# Power.net
KiCad netlist of a schematic drawn in Altium Designer
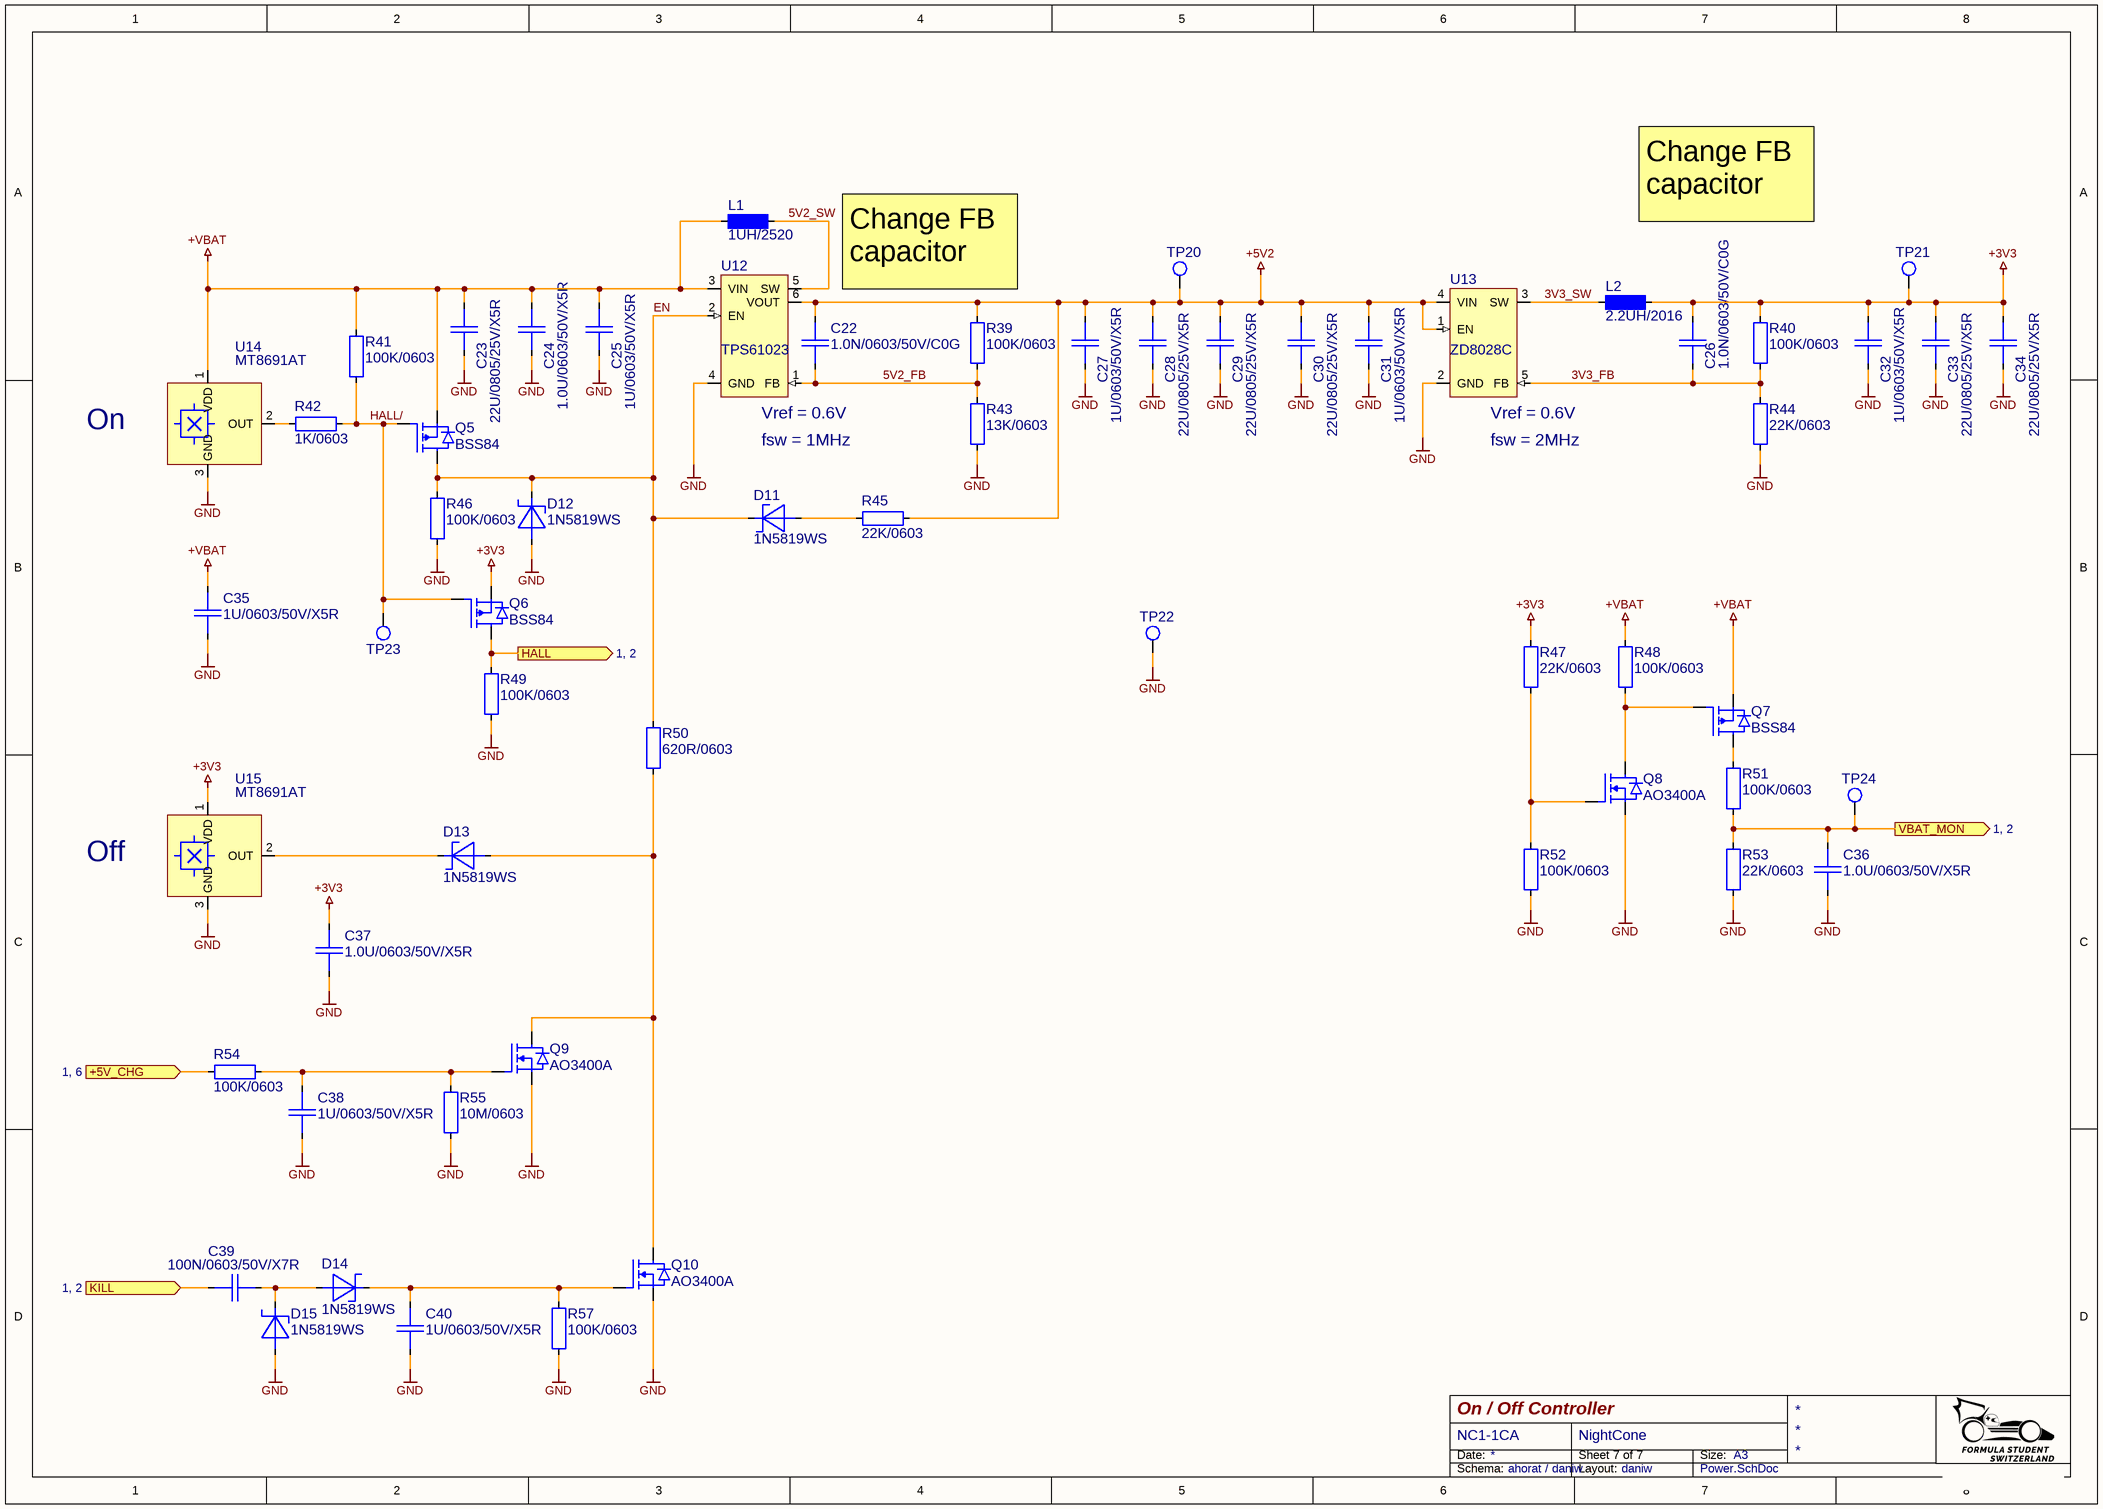
[diagram p0: Power.SchDoc]

(export (version "E")
  (design (tool "Eeschema 10.0.6"))
  (components
    (comp (ref "C22")
      (value "1.0N/0603/50V/C0G")
      (footprint "CAP0603_C0G")
      (description "CAP SM 0603 1.0nF 50V C0G")
      (fields (field (name "MANUFACTURER") "GENERIC"))
      (libsource (lib "daniw_altium_lib") (part "C"))
    )
    (comp (ref "C23")
      (value "22U/0805/25V/X5R")
      (footprint "CAP0805_X7R")
      (description "CAP SM 0805 22uF 25V X5R")
      (fields (field (name "MANUFACTURER") "GENERIC"))
      (libsource (lib "daniw_altium_lib") (part "C"))
    )
    (comp (ref "C24")
      (value "1.0U/0603/50V/X5R")
      (footprint "CAP0603_X7R")
      (description "CAP SM 0603 1.0uF 50V X5R")
      (fields (field (name "MANUFACTURER") "GENERIC"))
      (libsource (lib "daniw_altium_lib") (part "C"))
    )
    (comp (ref "C25")
      (value "1U/0603/50V/X5R")
      (footprint "CAP0603_X7R")
      (description "CAP SM 0603 1.0uF 50V X5R")
      (fields (field (name "MANUFACTURER") "GENERIC"))
      (libsource (lib "daniw_altium_lib") (part "C"))
    )
    (comp (ref "C26")
      (value "1.0N/0603/50V/C0G")
      (footprint "CAP0603_C0G")
      (description "CAP SM 0603 1.0nF 50V C0G")
      (fields (field (name "MANUFACTURER") "GENERIC"))
      (libsource (lib "daniw_altium_lib") (part "C"))
    )
    (comp (ref "C27")
      (value "1U/0603/50V/X5R")
      (footprint "CAP0603_X7R")
      (description "CAP SM 0603 1.0uF 50V X5R")
      (fields (field (name "MANUFACTURER") "GENERIC"))
      (libsource (lib "daniw_altium_lib") (part "C"))
    )
    (comp (ref "C28")
      (value "22U/0805/25V/X5R")
      (footprint "CAP0805_X7R")
      (description "CAP SM 0805 22uF 25V X5R")
      (fields (field (name "MANUFACTURER") "GENERIC"))
      (libsource (lib "daniw_altium_lib") (part "C"))
    )
    (comp (ref "C29")
      (value "22U/0805/25V/X5R")
      (footprint "CAP0805_X7R")
      (description "CAP SM 0805 22uF 25V X5R")
      (fields (field (name "MANUFACTURER") "GENERIC"))
      (libsource (lib "daniw_altium_lib") (part "C"))
    )
    (comp (ref "C30")
      (value "22U/0805/25V/X5R")
      (footprint "CAP0805_X7R")
      (description "CAP SM 0805 22uF 25V X5R")
      (fields (field (name "MANUFACTURER") "GENERIC"))
      (libsource (lib "daniw_altium_lib") (part "C"))
    )
    (comp (ref "C31")
      (value "1U/0603/50V/X5R")
      (footprint "CAP0603_X7R")
      (description "CAP SM 0603 1.0uF 50V X5R")
      (fields (field (name "MANUFACTURER") "GENERIC"))
      (libsource (lib "daniw_altium_lib") (part "C"))
    )
    (comp (ref "C32")
      (value "1U/0603/50V/X5R")
      (footprint "CAP0603_X7R")
      (description "CAP SM 0603 1.0uF 50V X5R")
      (fields (field (name "MANUFACTURER") "GENERIC"))
      (libsource (lib "daniw_altium_lib") (part "C"))
    )
    (comp (ref "C33")
      (value "22U/0805/25V/X5R")
      (footprint "CAP0805_X7R")
      (description "CAP SM 0805 22uF 25V X5R")
      (fields (field (name "MANUFACTURER") "GENERIC"))
      (libsource (lib "daniw_altium_lib") (part "C"))
    )
    (comp (ref "C34")
      (value "22U/0805/25V/X5R")
      (footprint "CAP0805_X7R")
      (description "CAP SM 0805 22uF 25V X5R")
      (fields (field (name "MANUFACTURER") "GENERIC"))
      (libsource (lib "daniw_altium_lib") (part "C"))
    )
    (comp (ref "C35")
      (value "1U/0603/50V/X5R")
      (footprint "CAP0603_X7R")
      (description "CAP SM 0603 1.0uF 50V X5R")
      (fields (field (name "MANUFACTURER") "GENERIC"))
      (libsource (lib "daniw_altium_lib") (part "C"))
    )
    (comp (ref "C36")
      (value "1.0U/0603/50V/X5R")
      (footprint "CAP0603_X7R")
      (description "CAP SM 0603 1.0uF 50V X5R")
      (fields (field (name "MANUFACTURER") "GENERIC"))
      (libsource (lib "daniw_altium_lib") (part "C"))
    )
    (comp (ref "C37")
      (value "1.0U/0603/50V/X5R")
      (footprint "CAP0603_X7R")
      (description "CAP SM 0603 1.0uF 50V X5R")
      (fields (field (name "MANUFACTURER") "GENERIC"))
      (libsource (lib "daniw_altium_lib") (part "C"))
    )
    (comp (ref "C38")
      (value "1U/0603/50V/X5R")
      (footprint "CAP0603_X7R")
      (description "CAP SM 0603 1.0uF 50V X5R")
      (fields (field (name "MANUFACTURER") "GENERIC"))
      (libsource (lib "daniw_altium_lib") (part "C"))
    )
    (comp (ref "C39")
      (value "100N/0603/50V/X7R")
      (footprint "CAP0603_X7R")
      (description "CAP SM 0603 100nF 50V X7R")
      (fields (field (name "MANUFACTURER") "GENERIC"))
      (libsource (lib "daniw_altium_lib") (part "C"))
    )
    (comp (ref "C40")
      (value "1U/0603/50V/X5R")
      (footprint "CAP0603_X7R")
      (description "CAP SM 0603 1.0uF 50V X5R")
      (fields (field (name "MANUFACTURER") "GENERIC"))
      (libsource (lib "daniw_altium_lib") (part "C"))
    )
    (comp (ref "D11")
      (value "1N5819WS")
      (footprint "SOD2513X100")
      (description "40V 600mV@1A 1A SOD-323 Schottky Barrier Diodes (SBD) ROHS")
      (fields (field (name "MANUFACTURER") "GENERIC"))
      (libsource (lib "daniw_altium_lib") (part "D_Schottky"))
    )
    (comp (ref "D12")
      (value "1N5819WS")
      (footprint "SOD2513X100")
      (description "40V 600mV@1A 1A SOD-323 Schottky Barrier Diodes (SBD) ROHS")
      (fields (field (name "MANUFACTURER") "GENERIC"))
      (libsource (lib "daniw_altium_lib") (part "D_Schottky"))
    )
    (comp (ref "D13")
      (value "1N5819WS")
      (footprint "SOD2513X100")
      (description "40V 600mV@1A 1A SOD-323 Schottky Barrier Diodes (SBD) ROHS")
      (fields (field (name "MANUFACTURER") "GENERIC"))
      (libsource (lib "daniw_altium_lib") (part "D_Schottky"))
    )
    (comp (ref "D14")
      (value "1N5819WS")
      (footprint "SOD2513X100")
      (description "40V 600mV@1A 1A SOD-323 Schottky Barrier Diodes (SBD) ROHS")
      (fields (field (name "MANUFACTURER") "GENERIC"))
      (libsource (lib "daniw_altium_lib") (part "D_Schottky"))
    )
    (comp (ref "D15")
      (value "1N5819WS")
      (footprint "SOD2513X100")
      (description "40V 600mV@1A 1A SOD-323 Schottky Barrier Diodes (SBD) ROHS")
      (fields (field (name "MANUFACTURER") "GENERIC"))
      (libsource (lib "daniw_altium_lib") (part "D_Schottky"))
    )
    (comp (ref "L1")
      (value "1UH/2520")
      (footprint "INDM2520X10")
      (description "1UH 2520 Shielded Inductor SMD")
      (fields (field (name "MANUFACTURER") "GENERIC"))
      (libsource (lib "daniw_altium_lib") (part "L"))
    )
    (comp (ref "L2")
      (value "2.2UH/2016")
      (footprint "INDM2016X10")
      (description "2.2UH 2016 Shielded Inductor SMD")
      (fields (field (name "MANUFACTURER") "GENERIC"))
      (libsource (lib "daniw_altium_lib") (part "L"))
    )
    (comp (ref "Q5")
      (value "BSS84")
      (footprint "SOT2395P280X125-3-SE")
      (description "50V P-Channel MOSFET")
      (fields (field (name "MANUFACTURER") "GENERIC"))
      (libsource (lib "daniw_altium_lib") (part "MOSFET P_SOT23"))
    )
    (comp (ref "Q6")
      (value "BSS84")
      (footprint "SOT2395P280X125-3-SE")
      (description "50V P-Channel MOSFET")
      (fields (field (name "MANUFACTURER") "GENERIC"))
      (libsource (lib "daniw_altium_lib") (part "MOSFET P_SOT23"))
    )
    (comp (ref "Q7")
      (value "BSS84")
      (footprint "SOT2395P280X125-3-SE")
      (description "50V P-Channel MOSFET")
      (fields (field (name "MANUFACTURER") "GENERIC"))
      (libsource (lib "daniw_altium_lib") (part "MOSFET P_SOT23"))
    )
    (comp (ref "Q8")
      (value "AO3400A")
      (footprint "SOT2395P280X125-3-SE")
      (description "30V N-Channel MOSFET")
      (fields (field (name "MANUFACTURER") "Alpha & Omega Semiconductor"))
      (libsource (lib "daniw_altium_lib") (part "MOSFET N_SOT23"))
    )
    (comp (ref "Q9")
      (value "AO3400A")
      (footprint "SOT2395P280X125-3-SE")
      (description "30V N-Channel MOSFET")
      (fields (field (name "MANUFACTURER") "Alpha & Omega Semiconductor"))
      (libsource (lib "daniw_altium_lib") (part "MOSFET N_SOT23"))
    )
    (comp (ref "Q10")
      (value "AO3400A")
      (footprint "SOT2395P280X125-3-SE")
      (description "30V N-Channel MOSFET")
      (fields (field (name "MANUFACTURER") "Alpha & Omega Semiconductor"))
      (libsource (lib "daniw_altium_lib") (part "MOSFET N_SOT23"))
    )
    (comp (ref "R39")
      (value "100K/0603")
      (footprint "R0603-0.40-WW")
      (description "RES SM 0603 100K")
      (fields (field (name "MANUFACTURER") "GENERIC"))
      (libsource (lib "daniw_altium_lib") (part "R"))
    )
    (comp (ref "R40")
      (value "100K/0603")
      (footprint "R0603-0.40-WW")
      (description "RES SM 0603 100K")
      (fields (field (name "MANUFACTURER") "GENERIC"))
      (libsource (lib "daniw_altium_lib") (part "R"))
    )
    (comp (ref "R41")
      (value "100K/0603")
      (footprint "R0603-0.40-WW")
      (description "RES SM 0603 100K")
      (fields (field (name "MANUFACTURER") "GENERIC"))
      (libsource (lib "daniw_altium_lib") (part "R"))
    )
    (comp (ref "R42")
      (value "1K/0603")
      (footprint "R0603-0.40-WW")
      (description "RES SM 0603 1K")
      (fields (field (name "MANUFACTURER") "GENERIC"))
      (libsource (lib "daniw_altium_lib") (part "R"))
    )
    (comp (ref "R43")
      (value "13K/0603")
      (footprint "R0603-0.40-WW")
      (description "RES SM 0603 13K")
      (fields (field (name "MANUFACTURER") "GENERIC"))
      (libsource (lib "daniw_altium_lib") (part "R"))
    )
    (comp (ref "R44")
      (value "22K/0603")
      (footprint "R0603-0.40-WW")
      (description "RES SM 0603 22K")
      (fields (field (name "MANUFACTURER") "GENERIC"))
      (libsource (lib "daniw_altium_lib") (part "R"))
    )
    (comp (ref "R45")
      (value "22K/0603")
      (footprint "R0603-0.40-WW")
      (description "RES SM 0603 22K")
      (fields (field (name "MANUFACTURER") "GENERIC"))
      (libsource (lib "daniw_altium_lib") (part "R"))
    )
    (comp (ref "R46")
      (value "100K/0603")
      (footprint "R0603-0.40-WW")
      (description "RES SM 0603 100K")
      (fields (field (name "MANUFACTURER") "GENERIC"))
      (libsource (lib "daniw_altium_lib") (part "R"))
    )
    (comp (ref "R47")
      (value "22K/0603")
      (footprint "R0603-0.40-WW")
      (description "RES SM 0603 22K")
      (fields (field (name "MANUFACTURER") "GENERIC"))
      (libsource (lib "daniw_altium_lib") (part "R"))
    )
    (comp (ref "R48")
      (value "100K/0603")
      (footprint "R0603-0.40-WW")
      (description "RES SM 0603 100K")
      (fields (field (name "MANUFACTURER") "GENERIC"))
      (libsource (lib "daniw_altium_lib") (part "R"))
    )
    (comp (ref "R49")
      (value "100K/0603")
      (footprint "R0603-0.40-WW")
      (description "RES SM 0603 100K")
      (fields (field (name "MANUFACTURER") "GENERIC"))
      (libsource (lib "daniw_altium_lib") (part "R"))
    )
    (comp (ref "R50")
      (value "620R/0603")
      (footprint "R0603-0.40-WW")
      (description "RES SM 0603 620R")
      (fields (field (name "MANUFACTURER") "GENERIC"))
      (libsource (lib "daniw_altium_lib") (part "R"))
    )
    (comp (ref "R51")
      (value "100K/0603")
      (footprint "R0603-0.40-WW")
      (description "RES SM 0603 100K")
      (fields (field (name "MANUFACTURER") "GENERIC"))
      (libsource (lib "daniw_altium_lib") (part "R"))
    )
    (comp (ref "R52")
      (value "100K/0603")
      (footprint "R0603-0.40-WW")
      (description "RES SM 0603 100K")
      (fields (field (name "MANUFACTURER") "GENERIC"))
      (libsource (lib "daniw_altium_lib") (part "R"))
    )
    (comp (ref "R53")
      (value "22K/0603")
      (footprint "R0603-0.40-WW")
      (description "RES SM 0603 22K")
      (fields (field (name "MANUFACTURER") "GENERIC"))
      (libsource (lib "daniw_altium_lib") (part "R"))
    )
    (comp (ref "R54")
      (value "100K/0603")
      (footprint "R0603-0.40-WW")
      (description "RES SM 0603 100K")
      (fields (field (name "MANUFACTURER") "GENERIC"))
      (libsource (lib "daniw_altium_lib") (part "R"))
    )
    (comp (ref "R55")
      (value "10M/0603")
      (footprint "R0603-0.40-WW")
      (description "RES SM 0603 10M")
      (fields (field (name "MANUFACTURER") "GENERIC"))
      (libsource (lib "daniw_altium_lib") (part "R"))
    )
    (comp (ref "R57")
      (value "100K/0603")
      (footprint "R0603-0.40-WW")
      (description "RES SM 0603 100K")
      (fields (field (name "MANUFACTURER") "GENERIC"))
      (libsource (lib "daniw_altium_lib") (part "R"))
    )
    (comp (ref "TP20")
      (value "TP_THD_1.5/0.8")
      (footprint "TP_THD_1.5/0.8")
      (description "THT Test Point 1.5/0.8mm")
      (fields (field (name "MANUFACTURER") "NONE"))
      (libsource (lib "daniw_altium_lib") (part "Testpoint"))
    )
    (comp (ref "TP21")
      (value "TP_THD_1.5/0.8")
      (footprint "TP_THD_1.5/0.8")
      (description "THT Test Point 1.5/0.8mm")
      (fields (field (name "MANUFACTURER") "NONE"))
      (libsource (lib "daniw_altium_lib") (part "Testpoint"))
    )
    (comp (ref "TP22")
      (value "TP_THD_1.5/0.8")
      (footprint "TP_THD_1.5/0.8")
      (description "THT Test Point 1.5/0.8mm")
      (fields (field (name "MANUFACTURER") "NONE"))
      (libsource (lib "daniw_altium_lib") (part "Testpoint"))
    )
    (comp (ref "TP23")
      (value "TP_THD_1.5/0.8")
      (footprint "TP_THD_1.5/0.8")
      (description "THT Test Point 1.5/0.8mm")
      (fields (field (name "MANUFACTURER") "NONE"))
      (libsource (lib "daniw_altium_lib") (part "Testpoint"))
    )
    (comp (ref "TP24")
      (value "TP_THD_1.5/0.8")
      (footprint "TP_THD_1.5/0.8")
      (description "THT Test Point 1.5/0.8mm")
      (fields (field (name "MANUFACTURER") "NONE"))
      (libsource (lib "daniw_altium_lib") (part "Testpoint"))
    )
    (comp (ref "U12")
      (value "TPS61023")
      (footprint "SOT50P160X60-6-SE")
      (description "3.7-A Boost Converter with 0.5-V Ultra-low Input Voltage")
      (fields (field (name "MANUFACTURER") "Texas Instruments"))
      (libsource (lib "daniw_altium_lib") (part "TPS61023"))
    )
    (comp (ref "U13")
      (value "ZD8028C")
      (footprint "SOT2395P280X125-5-SW")
      (description "1.5A 2MHz 5.5V Synchronous Buck Converter")
      (fields (field (name "MANUFACTURER") "Zetta"))
      (libsource (lib "daniw_altium_lib") (part "ZD8028C"))
    )
    (comp (ref "U14")
      (value "MT8691AT")
      (footprint "SOT2395P280X125-3-SE")
      (description "MT8691AT Uni-polar, Nano Power Hall-Effect Switch IC")
      (fields (field (name "MANUFACTURER") "Magn Tek"))
      (libsource (lib "daniw_altium_lib") (part "UHE4913"))
    )
    (comp (ref "U15")
      (value "MT8691AT")
      (footprint "SOT2395P280X125-3-SE")
      (description "MT8691AT Uni-polar, Nano Power Hall-Effect Switch IC")
      (fields (field (name "MANUFACTURER") "Magn Tek"))
      (libsource (lib "daniw_altium_lib") (part "UHE4913"))
    )
  )
  (nets
    (net (code "1") (name "+3V3") (class "Default")
      (node (ref "C26") (pin "1") (pinfunction "1_1") (pintype "passive"))
      (node (ref "C32") (pin "2") (pinfunction "2_2") (pintype "passive"))
      (node (ref "C33") (pin "1") (pinfunction "1_1") (pintype "passive"))
      (node (ref "C34") (pin "1") (pinfunction "1_1") (pintype "passive"))
      (node (ref "C37") (pin "1") (pinfunction "1_1") (pintype "passive"))
      (node (ref "L2") (pin "2") (pinfunction "2_2") (pintype "passive"))
      (node (ref "Q6") (pin "2") (pinfunction "SOURCE_2") (pintype "passive"))
      (node (ref "R40") (pin "1") (pinfunction "1_1") (pintype "passive"))
      (node (ref "R47") (pin "1") (pinfunction "1_1") (pintype "passive"))
      (node (ref "TP21") (pin "1") (pinfunction "1_1") (pintype "passive"))
      (node (ref "U15") (pin "1") (pinfunction "VDD_1") (pintype "passive"))
    )
    (net (code "2") (name "+5V2") (class "Default")
      (node (ref "C22") (pin "1") (pinfunction "1_1") (pintype "passive"))
      (node (ref "C27") (pin "2") (pinfunction "2_2") (pintype "passive"))
      (node (ref "C28") (pin "1") (pinfunction "1_1") (pintype "passive"))
      (node (ref "C29") (pin "1") (pinfunction "1_1") (pintype "passive"))
      (node (ref "C30") (pin "1") (pinfunction "1_1") (pintype "passive"))
      (node (ref "C31") (pin "2") (pinfunction "2_2") (pintype "passive"))
      (node (ref "R39") (pin "1") (pinfunction "1_1") (pintype "passive"))
      (node (ref "R45") (pin "2") (pinfunction "2_2") (pintype "passive"))
      (node (ref "TP20") (pin "1") (pinfunction "1_1") (pintype "passive"))
      (node (ref "U12") (pin "6") (pinfunction "VOUT_6") (pintype "passive"))
      (node (ref "U13") (pin "1") (pinfunction "EN_1") (pintype "input"))
      (node (ref "U13") (pin "4") (pinfunction "VIN_4") (pintype "passive"))
    )
    (net (code "3") (name "+VBAT") (class "Default")
      (node (ref "C23") (pin "1") (pinfunction "1_1") (pintype "passive"))
      (node (ref "C24") (pin "2") (pinfunction "2_2") (pintype "passive"))
      (node (ref "C25") (pin "2") (pinfunction "2_2") (pintype "passive"))
      (node (ref "C35") (pin "1") (pinfunction "1_1") (pintype "passive"))
      (node (ref "L1") (pin "1") (pinfunction "1_1") (pintype "passive"))
      (node (ref "Q5") (pin "2") (pinfunction "SOURCE_2") (pintype "passive"))
      (node (ref "Q7") (pin "2") (pinfunction "SOURCE_2") (pintype "passive"))
      (node (ref "R41") (pin "1") (pinfunction "1_1") (pintype "passive"))
      (node (ref "R48") (pin "1") (pinfunction "1_1") (pintype "passive"))
      (node (ref "U12") (pin "3") (pinfunction "VIN_3") (pintype "passive"))
      (node (ref "U14") (pin "1") (pinfunction "VDD_1") (pintype "passive"))
    )
    (net (code "4") (name "/+5V_CHG") (class "Default")
      (node (ref "R54") (pin "1") (pinfunction "1_1") (pintype "passive"))
    )
    (net (code "5") (name "/3V3_FB") (class "Default")
      (node (ref "C26") (pin "2") (pinfunction "2_2") (pintype "passive"))
      (node (ref "R40") (pin "2") (pinfunction "2_2") (pintype "passive"))
      (node (ref "R44") (pin "1") (pinfunction "1_1") (pintype "passive"))
      (node (ref "U13") (pin "5") (pinfunction "FB_5") (pintype "input"))
    )
    (net (code "6") (name "/3V3_SW") (class "Default")
      (node (ref "L2") (pin "1") (pinfunction "1_1") (pintype "passive"))
      (node (ref "U13") (pin "3") (pinfunction "SW_3") (pintype "passive"))
    )
    (net (code "7") (name "/5V2_FB") (class "Default")
      (node (ref "C22") (pin "2") (pinfunction "2_2") (pintype "passive"))
      (node (ref "R39") (pin "2") (pinfunction "2_2") (pintype "passive"))
      (node (ref "R43") (pin "2") (pinfunction "2_2") (pintype "passive"))
      (node (ref "U12") (pin "1") (pinfunction "FB_1") (pintype "input"))
    )
    (net (code "8") (name "/5V2_SW") (class "Default")
      (node (ref "L1") (pin "2") (pinfunction "2_2") (pintype "passive"))
      (node (ref "U12") (pin "5") (pinfunction "SW_5") (pintype "passive"))
    )
    (net (code "9") (name "/EN") (class "Default")
      (node (ref "D11") (pin "1") (pinfunction "1_1") (pintype "passive"))
      (node (ref "D12") (pin "1") (pinfunction "1_1") (pintype "passive"))
      (node (ref "Q5") (pin "3") (pinfunction "DRAIN_3") (pintype "passive"))
      (node (ref "R46") (pin "1") (pinfunction "1_1") (pintype "passive"))
      (node (ref "R50") (pin "1") (pinfunction "1_1") (pintype "passive"))
      (node (ref "U12") (pin "2") (pinfunction "EN_2") (pintype "input"))
    )
    (net (code "10") (name "/HALL") (class "Default")
      (node (ref "Q6") (pin "3") (pinfunction "DRAIN_3") (pintype "passive"))
      (node (ref "R49") (pin "1") (pinfunction "1_1") (pintype "passive"))
    )
    (net (code "11") (name "/HALL{slash}") (class "Default")
      (node (ref "Q5") (pin "1") (pinfunction "GATE_1") (pintype "passive"))
      (node (ref "Q6") (pin "1") (pinfunction "GATE_1") (pintype "passive"))
      (node (ref "R41") (pin "2") (pinfunction "2_2") (pintype "passive"))
      (node (ref "R42") (pin "2") (pinfunction "2_2") (pintype "passive"))
      (node (ref "TP23") (pin "1") (pinfunction "1_1") (pintype "passive"))
    )
    (net (code "12") (name "/KILL") (class "Default")
      (node (ref "C39") (pin "1") (pinfunction "1_1") (pintype "passive"))
    )
    (net (code "13") (name "/VBAT_MON") (class "Default")
      (node (ref "C36") (pin "1") (pinfunction "1_1") (pintype "passive"))
      (node (ref "R51") (pin "2") (pinfunction "2_2") (pintype "passive"))
      (node (ref "R53") (pin "1") (pinfunction "1_1") (pintype "passive"))
      (node (ref "TP24") (pin "1") (pinfunction "1_1") (pintype "passive"))
    )
    (net (code "14") (name "GND") (class "Default")
      (node (ref "C23") (pin "2") (pinfunction "2_2") (pintype "passive"))
      (node (ref "C24") (pin "1") (pinfunction "1_1") (pintype "passive"))
      (node (ref "C25") (pin "1") (pinfunction "1_1") (pintype "passive"))
      (node (ref "C27") (pin "1") (pinfunction "1_1") (pintype "passive"))
      (node (ref "C28") (pin "2") (pinfunction "2_2") (pintype "passive"))
      (node (ref "C29") (pin "2") (pinfunction "2_2") (pintype "passive"))
      (node (ref "C30") (pin "2") (pinfunction "2_2") (pintype "passive"))
      (node (ref "C31") (pin "1") (pinfunction "1_1") (pintype "passive"))
      (node (ref "C32") (pin "1") (pinfunction "1_1") (pintype "passive"))
      (node (ref "C33") (pin "2") (pinfunction "2_2") (pintype "passive"))
      (node (ref "C34") (pin "2") (pinfunction "2_2") (pintype "passive"))
      (node (ref "C35") (pin "2") (pinfunction "2_2") (pintype "passive"))
      (node (ref "C36") (pin "2") (pinfunction "2_2") (pintype "passive"))
      (node (ref "C37") (pin "2") (pinfunction "2_2") (pintype "passive"))
      (node (ref "C38") (pin "2") (pinfunction "2_2") (pintype "passive"))
      (node (ref "C40") (pin "2") (pinfunction "2_2") (pintype "passive"))
      (node (ref "D12") (pin "2") (pinfunction "2_2") (pintype "passive"))
      (node (ref "D15") (pin "2") (pinfunction "2_2") (pintype "passive"))
      (node (ref "Q10") (pin "2") (pinfunction "SOURCE_2") (pintype "passive"))
      (node (ref "Q8") (pin "2") (pinfunction "SOURCE_2") (pintype "passive"))
      (node (ref "Q9") (pin "2") (pinfunction "SOURCE_2") (pintype "passive"))
      (node (ref "R43") (pin "1") (pinfunction "1_1") (pintype "passive"))
      (node (ref "R44") (pin "2") (pinfunction "2_2") (pintype "passive"))
      (node (ref "R46") (pin "2") (pinfunction "2_2") (pintype "passive"))
      (node (ref "R49") (pin "2") (pinfunction "2_2") (pintype "passive"))
      (node (ref "R52") (pin "2") (pinfunction "2_2") (pintype "passive"))
      (node (ref "R53") (pin "2") (pinfunction "2_2") (pintype "passive"))
      (node (ref "R55") (pin "2") (pinfunction "2_2") (pintype "passive"))
      (node (ref "R57") (pin "2") (pinfunction "2_2") (pintype "passive"))
      (node (ref "TP22") (pin "1") (pinfunction "1_1") (pintype "passive"))
      (node (ref "U12") (pin "4") (pinfunction "GND_4") (pintype "passive"))
      (node (ref "U13") (pin "2") (pinfunction "GND_2") (pintype "passive"))
      (node (ref "U14") (pin "3") (pinfunction "GND_3") (pintype "passive"))
      (node (ref "U15") (pin "3") (pinfunction "GND_3") (pintype "passive"))
    )
    (net (code "15") (name "Net-(C39-Pad2)") (class "Default")
      (node (ref "C39") (pin "2") (pinfunction "2_2") (pintype "passive"))
      (node (ref "D14") (pin "2") (pinfunction "2_2") (pintype "passive"))
      (node (ref "D15") (pin "1") (pinfunction "1_1") (pintype "passive"))
    )
    (net (code "16") (name "Net-(D11-Pad2)") (class "Default")
      (node (ref "D11") (pin "2") (pinfunction "2_2") (pintype "passive"))
      (node (ref "R45") (pin "1") (pinfunction "1_1") (pintype "passive"))
    )
    (net (code "17") (name "Net-(Q7-DRAIN)") (class "Default")
      (node (ref "Q7") (pin "3") (pinfunction "DRAIN_3") (pintype "passive"))
      (node (ref "R51") (pin "1") (pinfunction "1_1") (pintype "passive"))
    )
    (net (code "18") (name "Net-(Q7-GATE)") (class "Default")
      (node (ref "Q7") (pin "1") (pinfunction "GATE_1") (pintype "passive"))
      (node (ref "Q8") (pin "3") (pinfunction "DRAIN_3") (pintype "passive"))
      (node (ref "R48") (pin "2") (pinfunction "2_2") (pintype "passive"))
    )
    (net (code "19") (name "Net-(Q8-GATE)") (class "Default")
      (node (ref "Q8") (pin "1") (pinfunction "GATE_1") (pintype "passive"))
      (node (ref "R47") (pin "2") (pinfunction "2_2") (pintype "passive"))
      (node (ref "R52") (pin "1") (pinfunction "1_1") (pintype "passive"))
    )
    (net (code "20") (name "Net-(Q9-GATE)") (class "Default")
      (node (ref "C38") (pin "1") (pinfunction "1_1") (pintype "passive"))
      (node (ref "Q9") (pin "1") (pinfunction "GATE_1") (pintype "passive"))
      (node (ref "R54") (pin "2") (pinfunction "2_2") (pintype "passive"))
      (node (ref "R55") (pin "1") (pinfunction "1_1") (pintype "passive"))
    )
    (net (code "21") (name "Net-(Q10-DRAIN)") (class "Default")
      (node (ref "D13") (pin "2") (pinfunction "2_2") (pintype "passive"))
      (node (ref "Q10") (pin "3") (pinfunction "DRAIN_3") (pintype "passive"))
      (node (ref "Q9") (pin "3") (pinfunction "DRAIN_3") (pintype "passive"))
      (node (ref "R50") (pin "2") (pinfunction "2_2") (pintype "passive"))
    )
    (net (code "22") (name "Net-(Q10-GATE)") (class "Default")
      (node (ref "C40") (pin "1") (pinfunction "1_1") (pintype "passive"))
      (node (ref "D14") (pin "1") (pinfunction "1_1") (pintype "passive"))
      (node (ref "Q10") (pin "1") (pinfunction "GATE_1") (pintype "passive"))
      (node (ref "R57") (pin "1") (pinfunction "1_1") (pintype "passive"))
    )
    (net (code "23") (name "Net-(U14-OUT)") (class "Default")
      (node (ref "R42") (pin "1") (pinfunction "1_1") (pintype "passive"))
      (node (ref "U14") (pin "2") (pinfunction "OUT_2") (pintype "open_collector"))
    )
    (net (code "24") (name "Net-(U15-OUT)") (class "Default")
      (node (ref "D13") (pin "1") (pinfunction "1_1") (pintype "passive"))
      (node (ref "U15") (pin "2") (pinfunction "OUT_2") (pintype "open_collector"))
    )
  )
)
